# RS485_Node.net
KiCad netlist of a schematic drawn in Altium Designer
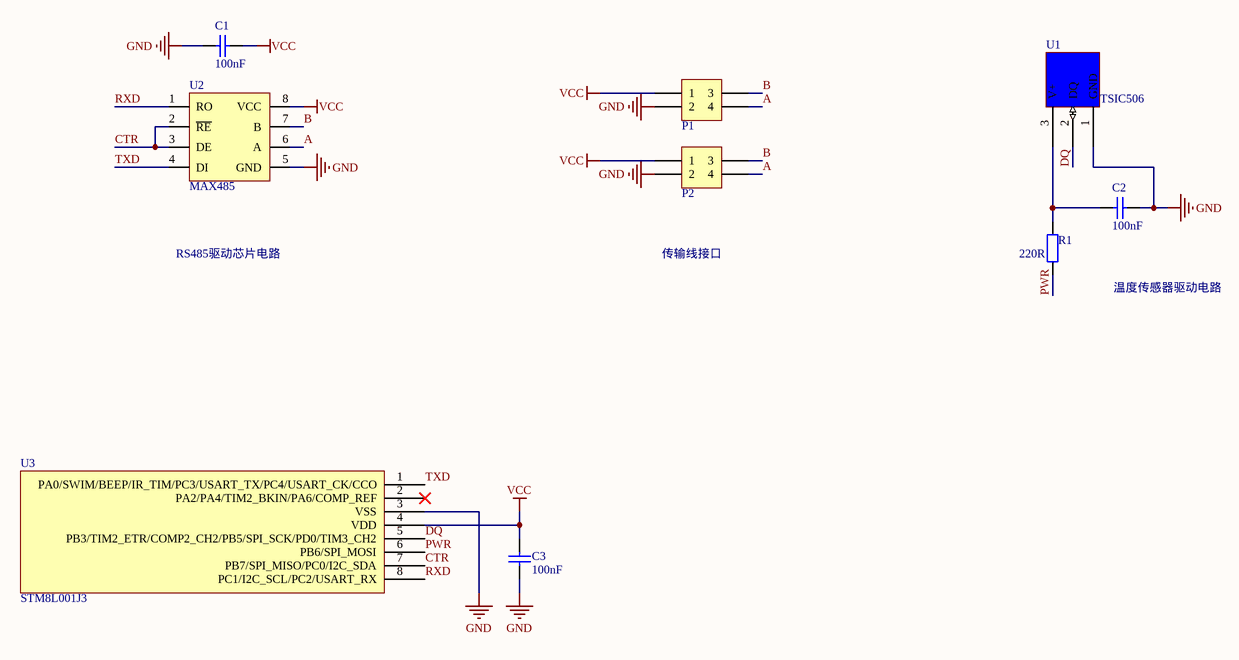
[diagram p0: RS485_Node.SchDoc]

(export (version "E")
  (design (tool "Eeschema 10.0.6"))
  (components
    (comp (ref "C1")
      (value "100nF")
      (footprint "C_0603")
      (description "无极性电容")
      (fields (field (name "Comment") "Cap") (field (name "PUBLISHER") "Altium Limited"))
      (libsource (lib "我的") (part "Cap"))
    )
    (comp (ref "C2")
      (value "100nF")
      (footprint "C_0603")
      (description "无极性电容")
      (fields (field (name "Comment") "Cap") (field (name "PUBLISHER") "Altium Limited"))
      (libsource (lib "我的") (part "Cap"))
    )
    (comp (ref "C3")
      (value "100nF")
      (footprint "C_0603")
      (description "无极性电容")
      (fields (field (name "Comment") "Cap") (field (name "PUBLISHER") "Altium Limited"))
      (libsource (lib "我的") (part "Cap"))
    )
    (comp (ref "P1")
      (value "Header 2X2B")
      (footprint "CONN_4PIN")
      (description "接插件")
      (fields (field (name "PUBLISHER") "Altium Limited"))
      (libsource (lib "我的") (part "Header 2X2B"))
    )
    (comp (ref "P2")
      (value "Header 2X2B")
      (footprint "CONN_4PIN")
      (description "接插件")
      (fields (field (name "PUBLISHER") "Altium Limited"))
      (libsource (lib "我的") (part "Header 2X2B"))
    )
    (comp (ref "R1")
      (value "220R")
      (footprint "R_0603")
      (description "贴片电阻")
      (fields (field (name "Comment") "Res1") (field (name "PUBLISHER") "Altium Limited"))
      (libsource (lib "我的") (part "Res1"))
    )
    (comp (ref "U1")
      (value "TSIC506")
      (footprint "TO92UA_A")
      (description "TSic TM系列芯片采用基于世界领先水平的专业校准技术对温度传感器进行预先校准，测量使用简单，可长期稳定地达到高精度效果。")
      (libsource (lib "RF") (part "TSIC506"))
    )
    (comp (ref "U2") (value "MAX485") (footprint "SOIC_8") (libsource (lib "RF") (part "MAX485")))
    (comp (ref "U3") (value "STM8L001J3") (footprint "SOIC_8") (libsource (lib "RF") (part "STM8L001J3")))
  )
  (nets
    (net (code "1") (name "/A") (class "Default")
      (node (ref "P1") (pin "4") (pinfunction "4_4") (pintype "passive"))
      (node (ref "P2") (pin "4") (pinfunction "4_4") (pintype "passive"))
      (node (ref "U2") (pin "6") (pinfunction "A_6") (pintype "passive"))
    )
    (net (code "2") (name "/B") (class "Default")
      (node (ref "P1") (pin "3") (pinfunction "3_3") (pintype "passive"))
      (node (ref "P2") (pin "3") (pinfunction "3_3") (pintype "passive"))
      (node (ref "U2") (pin "7") (pinfunction "B_7") (pintype "passive"))
    )
    (net (code "3") (name "/CTR") (class "Default")
      (node (ref "U2") (pin "2") (pinfunction "~{RE}_2") (pintype "passive"))
      (node (ref "U2") (pin "3") (pinfunction "DE_3") (pintype "passive"))
      (node (ref "U3") (pin "7") (pinfunction "PB7/SPI_MISO/PC0/I2C_SDA_7") (pintype "passive"))
    )
    (net (code "4") (name "/DQ") (class "Default")
      (node (ref "U1") (pin "2") (pinfunction "DQ_2") (pintype "bidirectional"))
      (node (ref "U3") (pin "5") (pinfunction "PB3/TIM2_ETR/COMP2_CH2/PB5/SPI_SCK/PD0/TIM3_CH2_5") (pintype "passive"))
    )
    (net (code "5") (name "/PWR") (class "Default")
      (node (ref "R1") (pin "1") (pinfunction "1_1") (pintype "passive"))
      (node (ref "U3") (pin "6") (pinfunction "PB6/SPI_MOSI_6") (pintype "passive"))
    )
    (net (code "6") (name "/RXD") (class "Default")
      (node (ref "U2") (pin "1") (pinfunction "RO_1") (pintype "passive"))
      (node (ref "U3") (pin "8") (pinfunction "PC1/I2C_SCL/PC2/USART_RX_8") (pintype "passive"))
    )
    (net (code "7") (name "/TXD") (class "Default")
      (node (ref "U2") (pin "4") (pinfunction "DI_4") (pintype "passive"))
      (node (ref "U3") (pin "1") (pinfunction "PA0/SWIM/BEEP/IR_TIM/PC3/USART_TX/PC4/USART_CK/CCO_1") (pintype "passive"))
    )
    (net (code "8") (name "GND") (class "Default")
      (node (ref "C1") (pin "1") (pinfunction "1_1") (pintype "passive"))
      (node (ref "C2") (pin "2") (pinfunction "2_2") (pintype "passive"))
      (node (ref "C3") (pin "2") (pinfunction "2_2") (pintype "passive"))
      (node (ref "P1") (pin "2") (pinfunction "2_2") (pintype "passive"))
      (node (ref "P2") (pin "2") (pinfunction "2_2") (pintype "passive"))
      (node (ref "U1") (pin "1") (pinfunction "GND_1") (pintype "power_in"))
      (node (ref "U2") (pin "5") (pinfunction "GND_5") (pintype "power_in"))
      (node (ref "U3") (pin "3") (pinfunction "VSS_3") (pintype "passive"))
    )
    (net (code "9") (name "Net-(U1-V+)") (class "Default")
      (node (ref "C2") (pin "1") (pinfunction "1_1") (pintype "passive"))
      (node (ref "R1") (pin "2") (pinfunction "2_2") (pintype "passive"))
      (node (ref "U1") (pin "3") (pinfunction "V+_3") (pintype "power_in"))
    )
    (net (code "10") (name "VCC") (class "Default")
      (node (ref "C1") (pin "2") (pinfunction "2_2") (pintype "passive"))
      (node (ref "C3") (pin "1") (pinfunction "1_1") (pintype "passive"))
      (node (ref "P1") (pin "1") (pinfunction "1_1") (pintype "passive"))
      (node (ref "P2") (pin "1") (pinfunction "1_1") (pintype "passive"))
      (node (ref "U2") (pin "8") (pinfunction "VCC_8") (pintype "power_in"))
      (node (ref "U3") (pin "4") (pinfunction "VDD_4") (pintype "passive"))
    )
    (net (code "11") (name "unconnected-(U3-PA2{slash}PA4{slash}TIM2_BKIN{slash}PA6{slash}COMP_REF-Pad2)") (class "Default")
      (node (ref "U3") (pin "2") (pinfunction "PA2/PA4/TIM2_BKIN/PA6/COMP_REF_2") (pintype "passive+no_connect"))
    )
  )
)
